# Cyber_VCM.net
KiCad netlist of a schematic drawn in Altium Designer
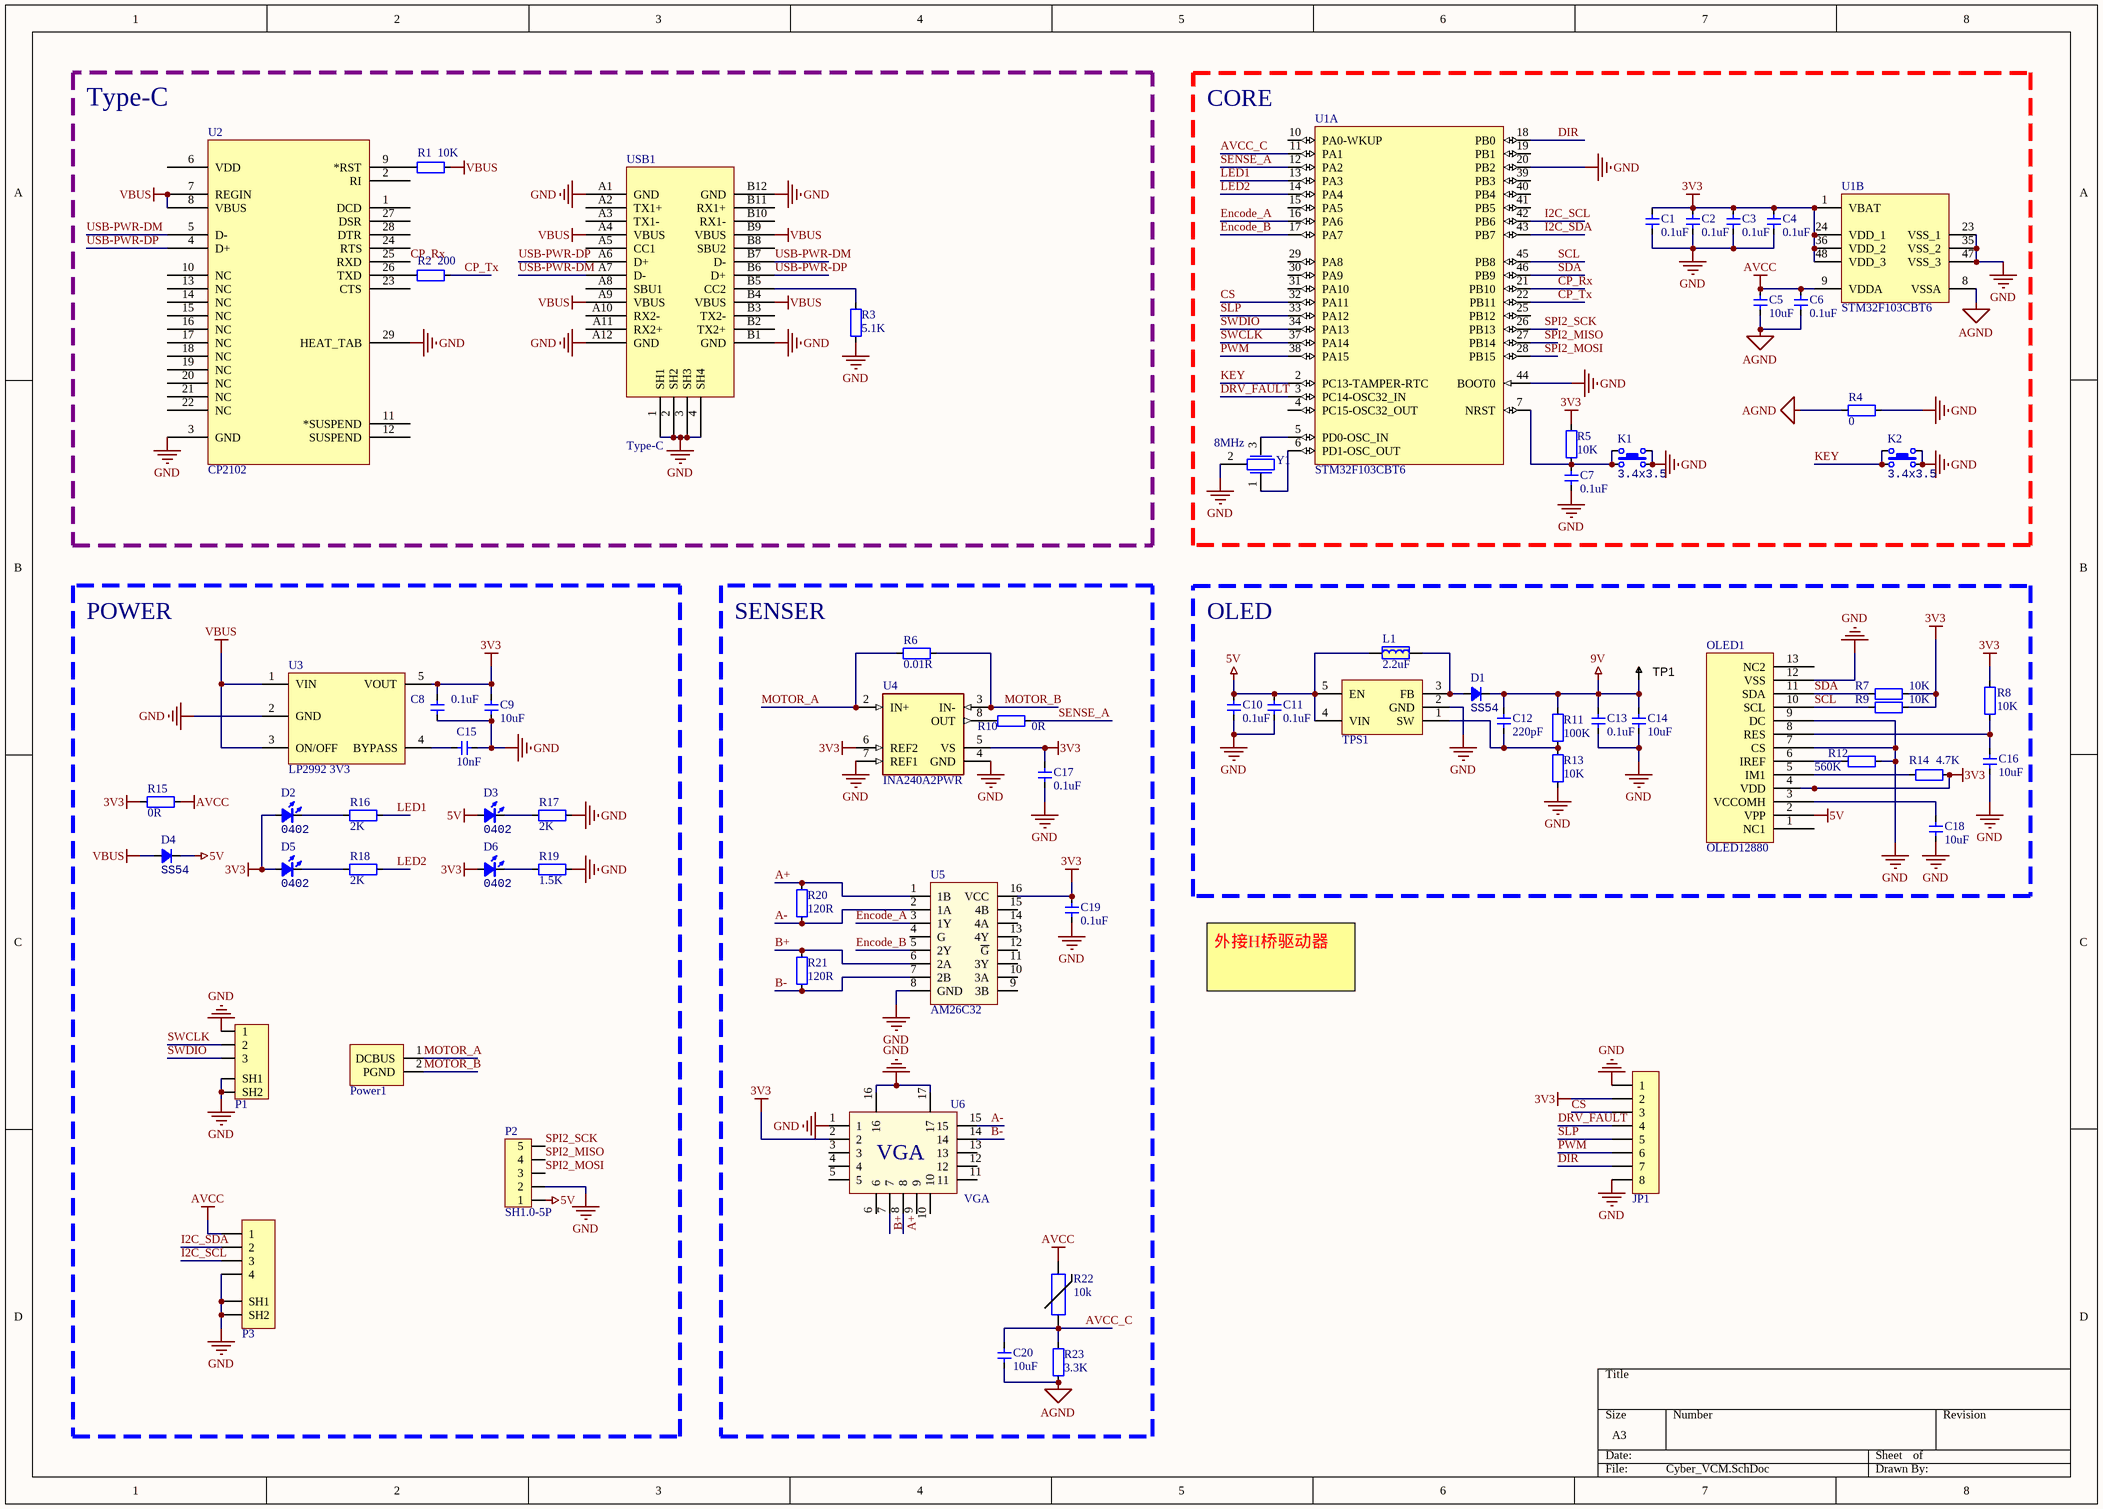
[diagram p0: Cyber_VCM.SchDoc]

(export (version "E")
  (design (tool "Eeschema 10.0.6"))
  (components
    (comp (ref "C1")
      (value "0.1uF")
      (footprint "CAP_0402")
      (description "Capacitor")
      (libsource (lib "Cyber_VCM") (part "电容-0402"))
    )
    (comp (ref "C2")
      (value "0.1uF")
      (footprint "CAP_0402")
      (description "Capacitor")
      (libsource (lib "Cyber_VCM") (part "电容-0402"))
    )
    (comp (ref "C3")
      (value "0.1uF")
      (footprint "CAP_0402")
      (description "Capacitor")
      (libsource (lib "Cyber_VCM") (part "电容-0402"))
    )
    (comp (ref "C4")
      (value "0.1uF")
      (footprint "CAP_0402")
      (description "Capacitor")
      (libsource (lib "Cyber_VCM") (part "电容-0402"))
    )
    (comp (ref "C5")
      (value "10uF")
      (footprint "CAP_0402")
      (description "Capacitor")
      (libsource (lib "Cyber_VCM") (part "电容-0402"))
    )
    (comp (ref "C6")
      (value "0.1uF")
      (footprint "CAP_0402")
      (description "Capacitor")
      (libsource (lib "Cyber_VCM") (part "电容-0402"))
    )
    (comp (ref "C7")
      (value "0.1uF")
      (footprint "CAP_0402")
      (description "Capacitor")
      (libsource (lib "MyPcbLib") (part "电容-0402"))
    )
    (comp (ref "C8")
      (value "0.1uF")
      (footprint "CAP_0402")
      (description "Capacitor")
      (libsource (lib "Cyber_VCM") (part "电容-0402"))
    )
    (comp (ref "C9")
      (value "10uF")
      (footprint "CAP_0402")
      (description "Capacitor")
      (libsource (lib "Cyber_VCM") (part "电容-0402"))
    )
    (comp (ref "C10")
      (value "0.1uF")
      (footprint "CAP_0402")
      (description "Capacitor")
      (libsource (lib "Serena-Ctrl") (part "电容-0402"))
    )
    (comp (ref "C11")
      (value "0.1uF")
      (footprint "CAP_0402")
      (description "Capacitor")
      (libsource (lib "Serena-Ctrl") (part "电容-0402"))
    )
    (comp (ref "C12")
      (value "220pF")
      (footprint "CAP_0402")
      (description "Capacitor")
      (libsource (lib "Serena-Ctrl") (part "电容-0402"))
    )
    (comp (ref "C13")
      (value "0.1uF")
      (footprint "0603-CAP")
      (description "Capacitor")
      (libsource (lib "Serena-Ctrl") (part "电容-0603"))
    )
    (comp (ref "C14")
      (value "10uF")
      (footprint "0603-CAP")
      (description "Capacitor")
      (libsource (lib "Serena-Ctrl") (part "电容-0603"))
    )
    (comp (ref "C15")
      (value "10nF")
      (footprint "CAP_0402")
      (description "Capacitor")
      (libsource (lib "Cyber_VCM") (part "电容-0402"))
    )
    (comp (ref "C16")
      (value "10uF")
      (footprint "CAP_0402")
      (description "Capacitor")
      (libsource (lib "MyPcbLib") (part "电容-0402"))
    )
    (comp (ref "C17")
      (value "0.1uF")
      (footprint "CAP_0402")
      (description "Capacitor")
      (libsource (lib "MyPcbLib") (part "电容-0402"))
    )
    (comp (ref "C18")
      (value "10uF")
      (footprint "CAP_0402")
      (description "Capacitor")
      (libsource (lib "MyPcbLib") (part "电容-0402"))
    )
    (comp (ref "C19")
      (value "0.1uF")
      (footprint "0603-CAP")
      (description "Capacitor")
      (libsource (lib "VCM_Ctrl") (part "电容-0603"))
    )
    (comp (ref "C20")
      (value "10uF")
      (footprint "CAP_0402")
      (description "Capacitor")
      (libsource (lib "MyPcbLib") (part "电容-0402"))
    )
    (comp (ref "D1")
      (value "SS54")
      (footprint "DO-214AC")
      (description "Diode")
      (libsource (lib "Serena-Ctrl") (part "Diode_SMA"))
    )
    (comp (ref "D2")
      (value "color?")
      (footprint "LED_0402_BLUE")
      (description "LED")
      (fields (field (name "TYPE") "0402"))
      (libsource (lib "Cyber_VCM") (part "LED_0402"))
    )
    (comp (ref "D3")
      (value "color?")
      (footprint "LED_0402_BLUE")
      (description "LED")
      (fields (field (name "TYPE") "0402"))
      (libsource (lib "Cyber_VCM") (part "LED_0402"))
    )
    (comp (ref "D4")
      (value "SS54")
      (footprint "DO-214AC")
      (description "Diode")
      (libsource (lib "Cyber_VCM") (part "Diode_SMA"))
    )
    (comp (ref "D5")
      (value "color?")
      (footprint "LED_0402_BLUE")
      (description "LED")
      (fields (field (name "TYPE") "0402"))
      (libsource (lib "Cyber_VCM") (part "LED_0402"))
    )
    (comp (ref "D6")
      (value "color?")
      (footprint "LED_0402_BLUE")
      (description "LED")
      (fields (field (name "TYPE") "0402"))
      (libsource (lib "Cyber_VCM") (part "LED_0402"))
    )
    (comp (ref "JP1")
      (value "HDR-1X8")
      (footprint "HDR2.54-M-LI-8P")
      (description "8P接插件")
      (fields (field (name "版权归属") "源创客"))
      (libsource (lib "Cyber_VCM") (part "Header 8"))
    )
    (comp (ref "K1")
      (value "3.4x3.5")
      (footprint "ButtonTACT_3.5*3.55_90")
      (description "Button")
      (fields (field (name "Comment") "TACT 4P"))
      (libsource (lib "KitSprout") (part "ButtonTACT"))
    )
    (comp (ref "K2")
      (value "3.4x3.5")
      (footprint "ButtonTACT_3.5*3.55_90")
      (description "Button")
      (fields (field (name "Comment") "TACT 4P"))
      (libsource (lib "KitSprout") (part "ButtonTACT"))
    )
    (comp (ref "L1")
      (value "2.2uF")
      (footprint "2520-L")
      (description "磁珠")
      (libsource (lib "Serena-Ctrl") (part "电感-0805"))
    )
    (comp (ref "OLED1")
      (value "OLED12880")
      (footprint "OLED12880")
      (description "12880寸OLED")
      (libsource (lib "Cyber_VCM") (part "OLED12880"))
    )
    (comp (ref "P1")
      (value "SH1.0-3P")
      (footprint "SH1.0-3P")
      (description "Header")
      (libsource (lib "Cyber_VCM") (part "SH1.0-3P"))
    )
    (comp (ref "P2") (value "SH1.0-5P") (footprint "SH1.0-5P") (libsource (lib "MyPcbLib") (part "SH1.0-5P")))
    (comp (ref "P3")
      (value "SH1.0-4P")
      (footprint "SH1.0-4P")
      (libsource (lib "Cyber_VCM") (part "SH1.0-4P"))
    )
    (comp (ref "Power1")
      (value "电源")
      (footprint "TX60电源")
      (description "12~24VDC电源")
      (libsource (lib "Cyber_VCM") (part "电源"))
    )
    (comp (ref "R1")
      (value "10K")
      (footprint "RES_0402")
      (description "Resistor")
      (libsource (lib "") (part "电阻-0402_1"))
    )
    (comp (ref "R2")
      (value "200")
      (footprint "RES_0402")
      (description "Resistor")
      (libsource (lib "") (part "电阻-0402_1"))
    )
    (comp (ref "R3")
      (value "5.1K")
      (footprint "RES_0402")
      (description "Resistor")
      (libsource (lib "") (part "电阻-0402_2"))
    )
    (comp (ref "R4")
      (value "0")
      (footprint "RES_0402")
      (description "Resistor")
      (libsource (lib "Cyber_VCM") (part "电阻-0402"))
    )
    (comp (ref "R5")
      (value "10K")
      (footprint "RES_0402")
      (description "Resistor")
      (libsource (lib "MyPcbLib") (part "电阻-0402"))
    )
    (comp (ref "R6")
      (value "0.01R")
      (footprint "1206-RES")
      (description "Resistor")
      (libsource (lib "MyPcbLib") (part "电阻-1206"))
    )
    (comp (ref "R7")
      (value "10K")
      (footprint "RES_0402")
      (description "Resistor")
      (libsource (lib "VectorController") (part "电阻-0402"))
    )
    (comp (ref "R8")
      (value "10K")
      (footprint "RES_0402")
      (description "Resistor")
      (libsource (lib "MyPcbLib") (part "电阻-0402"))
    )
    (comp (ref "R9")
      (value "10K")
      (footprint "RES_0402")
      (description "Resistor")
      (libsource (lib "VectorController") (part "电阻-0402"))
    )
    (comp (ref "R10")
      (value "0R")
      (footprint "RES_0402")
      (description "Resistor")
      (libsource (lib "Cyber_VCM") (part "电阻-0402"))
    )
    (comp (ref "R11")
      (value "100K")
      (footprint "RES_0402")
      (description "Resistor")
      (libsource (lib "Serena-Ctrl") (part "电阻-0402"))
    )
    (comp (ref "R12")
      (value "560K")
      (footprint "RES_0402")
      (description "Resistor")
      (libsource (lib "") (part "电阻-0402_3"))
    )
    (comp (ref "R13")
      (value "10K")
      (footprint "RES_0402")
      (description "Resistor")
      (libsource (lib "Serena-Ctrl") (part "电阻-0402"))
    )
    (comp (ref "R14")
      (value "4.7K")
      (footprint "RES_0402")
      (description "Resistor")
      (libsource (lib "") (part "电阻-0402_3"))
    )
    (comp (ref "R15")
      (value "0R")
      (footprint "RES_0402")
      (description "Resistor")
      (libsource (lib "") (part "电阻-0402_1"))
    )
    (comp (ref "R16")
      (value "2K")
      (footprint "RES_0402")
      (description "Resistor")
      (libsource (lib "Cyber_VCM") (part "电阻-0402"))
    )
    (comp (ref "R17")
      (value "2K")
      (footprint "RES_0402")
      (description "Resistor")
      (libsource (lib "Cyber_VCM") (part "电阻-0402"))
    )
    (comp (ref "R18")
      (value "2K")
      (footprint "RES_0402")
      (description "Resistor")
      (libsource (lib "Cyber_VCM") (part "电阻-0402"))
    )
    (comp (ref "R19")
      (value "1.5K")
      (footprint "RES_0402")
      (description "Resistor")
      (libsource (lib "Cyber_VCM") (part "电阻-0402"))
    )
    (comp (ref "R20")
      (value "120R")
      (footprint "RES_0603")
      (description "Resistor")
      (libsource (lib "Ctrl_FOC") (part "电阻-0603"))
    )
    (comp (ref "R21")
      (value "120R")
      (footprint "RES_0603")
      (description "Resistor")
      (libsource (lib "Ctrl_FOC") (part "电阻-0603"))
    )
    (comp (ref "R22")
      (value "10k")
      (footprint "RES_0402")
      (description "THERMISTOR 10K OHM NTC 0402 SMD")
      (fields (field (name "Comment") "NCP15XH103F03RC"))
      (libsource (lib "MyPcbLib") (part "NCP15XH103F03RC"))
    )
    (comp (ref "R23")
      (value "3.3K")
      (footprint "RES_0402")
      (description "Resistor")
      (libsource (lib "MyPcbLib") (part "电阻-0402"))
    )
    (comp (ref "TP1")
      (value "TESTPOINT")
      (footprint "TP-R30")
      (description "SMD test pin")
      (libsource (lib "Serena-Ctrl") (part "TESTPOINT"))
    )
    (comp (ref "TPS1")
      (value "TPS61040DBV")
      (footprint "SOT23-5")
      (libsource (lib "Serena-Ctrl") (part "TPS61040DBV"))
    )
    (comp (ref "U1")
      (value "STM32F103CBT6")
      (footprint "LQFP-48")
      (libsource (lib "Cyber_VCM") (part "STM32F103CBT6"))
    )
    (comp (ref "U2")
      (value "CP2102")
      (footprint "QFN-28")
      (description "USB转TTL")
      (libsource (lib "Cyber_VCM") (part "CP2102"))
    )
    (comp (ref "U3")
      (value "LP2992 3V3")
      (footprint "SOT23-5")
      (description "LDO")
      (libsource (lib "Cyber_VCM") (part "LP2992"))
    )
    (comp (ref "U4")
      (value "INA240A2PWR")
      (footprint "SOP65 P640X120-8N")
      (fields (field (name "MF") "Texas Instruments"))
      (libsource (lib "mLib") (part "INA240A2PWR"))
    )
    (comp (ref "U5")
      (value "AM26C32")
      (footprint "SOP16")
      (description "AM26C32 Quadruple Differential Line Receiver")
      (libsource (lib "VCM_Ctrl") (part "AM26C32"))
    )
    (comp (ref "U6") (value "VGA") (footprint "VGA15A") (libsource (lib "VCM_Ctrl") (part "VGA")))
    (comp (ref "USB1")
      (value "Type-C")
      (footprint "Type-C-TOP")
      (libsource (lib "Cyber_VCM") (part "USB-Type-C-TOP"))
    )
    (comp (ref "Y1")
      (value "8MHz")
      (footprint "晶振-3P")
      (description "村田贴片")
      (libsource (lib "MyPcbLib") (part "晶振-3Pin"))
    )
  )
  (nets
    (net (code "1") (name "/A+") (class "Default")
      (node (ref "R20") (pin "2") (pinfunction "2_2") (pintype "passive"))
      (node (ref "U5") (pin "1") (pinfunction "1B_1") (pintype "passive"))
      (node (ref "U6") (pin "8") (pinfunction "8_8") (pintype "passive"))
    )
    (net (code "2") (name "/A-") (class "Default")
      (node (ref "R20") (pin "1") (pinfunction "1_1") (pintype "passive"))
      (node (ref "U5") (pin "2") (pinfunction "1A_2") (pintype "passive"))
      (node (ref "U6") (pin "15") (pinfunction "15_15") (pintype "passive"))
    )
    (net (code "3") (name "/AVCC_C") (class "Default")
      (node (ref "C20") (pin "2") (pinfunction "2_2") (pintype "passive"))
      (node (ref "R22") (pin "1") (pinfunction "0_1") (pintype "passive"))
      (node (ref "R23") (pin "2") (pinfunction "2_2") (pintype "passive"))
      (node (ref "U1") (pin "11") (pinfunction "PA1_11") (pintype "bidirectional"))
    )
    (net (code "4") (name "/B+") (class "Default")
      (node (ref "R21") (pin "2") (pinfunction "2_2") (pintype "passive"))
      (node (ref "U5") (pin "6") (pinfunction "2A_6") (pintype "passive"))
      (node (ref "U6") (pin "7") (pinfunction "7_7") (pintype "passive"))
    )
    (net (code "5") (name "/B-") (class "Default")
      (node (ref "R21") (pin "1") (pinfunction "1_1") (pintype "passive"))
      (node (ref "U5") (pin "7") (pinfunction "2B_7") (pintype "passive"))
      (node (ref "U6") (pin "14") (pinfunction "14_14") (pintype "passive"))
    )
    (net (code "6") (name "/CP_Rx") (class "Default")
      (node (ref "U1") (pin "21") (pinfunction "PB10_21") (pintype "bidirectional"))
      (node (ref "U2") (pin "25") (pinfunction "RXD_25") (pintype "passive"))
    )
    (net (code "7") (name "/CP_Tx") (class "Default")
      (node (ref "R2") (pin "1") (pinfunction "1_1") (pintype "passive"))
      (node (ref "U1") (pin "22") (pinfunction "PB11_22") (pintype "bidirectional"))
    )
    (net (code "8") (name "/CS") (class "Default")
      (node (ref "JP1") (pin "3") (pinfunction "3_3") (pintype "passive"))
      (node (ref "U1") (pin "32") (pinfunction "PA11_32") (pintype "bidirectional"))
    )
    (net (code "9") (name "/DIR") (class "Default")
      (node (ref "JP1") (pin "7") (pinfunction "7_7") (pintype "passive"))
      (node (ref "U1") (pin "18") (pinfunction "PB0_18") (pintype "bidirectional"))
    )
    (net (code "10") (name "/DRV_FAULT") (class "Default")
      (node (ref "JP1") (pin "4") (pinfunction "4_4") (pintype "passive"))
      (node (ref "U1") (pin "3") (pinfunction "PC14-OSC32_IN_3") (pintype "bidirectional"))
    )
    (net (code "11") (name "/Encode_A") (class "Default")
      (node (ref "U1") (pin "16") (pinfunction "PA6_16") (pintype "bidirectional"))
      (node (ref "U5") (pin "3") (pinfunction "1Y_3") (pintype "passive"))
    )
    (net (code "12") (name "/Encode_B") (class "Default")
      (node (ref "U1") (pin "17") (pinfunction "PA7_17") (pintype "bidirectional"))
      (node (ref "U5") (pin "5") (pinfunction "2Y_5") (pintype "passive"))
    )
    (net (code "13") (name "/I2C_SCL") (class "Default")
      (node (ref "P3") (pin "3") (pinfunction "3_3") (pintype "passive"))
      (node (ref "U1") (pin "42") (pinfunction "PB6_42") (pintype "bidirectional"))
    )
    (net (code "14") (name "/I2C_SDA") (class "Default")
      (node (ref "P3") (pin "2") (pinfunction "2_2") (pintype "passive"))
      (node (ref "U1") (pin "43") (pinfunction "PB7_43") (pintype "bidirectional"))
    )
    (net (code "15") (name "/KEY") (class "Default")
      (node (ref "K2") (pin "1") (pinfunction "1_1") (pintype "passive"))
      (node (ref "K2") (pin "3") (pinfunction "3_3") (pintype "passive"))
      (node (ref "U1") (pin "2") (pinfunction "PC13-TAMPER-RTC_2") (pintype "bidirectional"))
    )
    (net (code "16") (name "/LED1") (class "Default")
      (node (ref "R16") (pin "2") (pinfunction "2_2") (pintype "passive"))
      (node (ref "U1") (pin "13") (pinfunction "PA3_13") (pintype "bidirectional"))
    )
    (net (code "17") (name "/LED2") (class "Default")
      (node (ref "R18") (pin "2") (pinfunction "2_2") (pintype "passive"))
      (node (ref "U1") (pin "14") (pinfunction "PA4_14") (pintype "bidirectional"))
    )
    (net (code "18") (name "/MOTOR_A") (class "Default")
      (node (ref "Power1") (pin "1") (pinfunction "DCBUS_1") (pintype "passive"))
      (node (ref "R6") (pin "1") (pinfunction "1_1") (pintype "passive"))
      (node (ref "U4") (pin "2") (pinfunction "IN+_2") (pintype "input"))
    )
    (net (code "19") (name "/MOTOR_B") (class "Default")
      (node (ref "Power1") (pin "2") (pinfunction "PGND_2") (pintype "passive"))
      (node (ref "R6") (pin "2") (pinfunction "2_2") (pintype "passive"))
      (node (ref "U4") (pin "3") (pinfunction "IN-_3") (pintype "input"))
    )
    (net (code "20") (name "/PWM") (class "Default")
      (node (ref "JP1") (pin "6") (pinfunction "6_6") (pintype "passive"))
      (node (ref "U1") (pin "38") (pinfunction "PA15_38") (pintype "bidirectional"))
    )
    (net (code "21") (name "/SCL") (class "Default")
      (node (ref "OLED1") (pin "10") (pinfunction "SCL_10") (pintype "passive"))
      (node (ref "R9") (pin "1") (pinfunction "1_1") (pintype "passive"))
      (node (ref "U1") (pin "45") (pinfunction "PB8_45") (pintype "bidirectional"))
    )
    (net (code "22") (name "/SDA") (class "Default")
      (node (ref "OLED1") (pin "11") (pinfunction "SDA_11") (pintype "passive"))
      (node (ref "R7") (pin "1") (pinfunction "1_1") (pintype "passive"))
      (node (ref "U1") (pin "46") (pinfunction "PB9_46") (pintype "bidirectional"))
    )
    (net (code "23") (name "/SENSE_A") (class "Default")
      (node (ref "R10") (pin "2") (pinfunction "2_2") (pintype "passive"))
      (node (ref "U1") (pin "12") (pinfunction "PA2_12") (pintype "bidirectional"))
    )
    (net (code "24") (name "/SLP") (class "Default")
      (node (ref "JP1") (pin "5") (pinfunction "5_5") (pintype "passive"))
      (node (ref "U1") (pin "33") (pinfunction "PA12_33") (pintype "bidirectional"))
    )
    (net (code "25") (name "/SPI2_MISO") (class "Default")
      (node (ref "P2") (pin "4") (pinfunction "4_4") (pintype "passive"))
      (node (ref "U1") (pin "27") (pinfunction "PB14_27") (pintype "bidirectional"))
    )
    (net (code "26") (name "/SPI2_MOSI") (class "Default")
      (node (ref "P2") (pin "3") (pinfunction "3_3") (pintype "passive"))
      (node (ref "U1") (pin "28") (pinfunction "PB15_28") (pintype "bidirectional"))
    )
    (net (code "27") (name "/SPI2_SCK") (class "Default")
      (node (ref "P2") (pin "5") (pinfunction "5_5") (pintype "passive"))
      (node (ref "U1") (pin "26") (pinfunction "PB13_26") (pintype "bidirectional"))
    )
    (net (code "28") (name "/SWCLK") (class "Default")
      (node (ref "P1") (pin "2") (pinfunction "2_2") (pintype "passive"))
      (node (ref "U1") (pin "37") (pinfunction "PA14_37") (pintype "bidirectional"))
    )
    (net (code "29") (name "/SWDIO") (class "Default")
      (node (ref "P1") (pin "3") (pinfunction "3_3") (pintype "passive"))
      (node (ref "U1") (pin "34") (pinfunction "PA13_34") (pintype "bidirectional"))
    )
    (net (code "30") (name "/USB-PWR-DM") (class "Default")
      (node (ref "U2") (pin "5") (pinfunction "D-_5") (pintype "passive"))
      (node (ref "USB1") (pin "A7") (pinfunction "D-_A7") (pintype "passive"))
      (node (ref "USB1") (pin "B7") (pinfunction "D-_B7") (pintype "passive"))
    )
    (net (code "31") (name "/USB-PWR-DP") (class "Default")
      (node (ref "U2") (pin "4") (pinfunction "D+_4") (pintype "passive"))
      (node (ref "USB1") (pin "A6") (pinfunction "D+_A6") (pintype "passive"))
      (node (ref "USB1") (pin "B6") (pinfunction "D+_B6") (pintype "passive"))
    )
    (net (code "32") (name "3V3") (class "Default")
      (node (ref "C1") (pin "2") (pinfunction "2_2") (pintype "passive"))
      (node (ref "C17") (pin "2") (pinfunction "2_2") (pintype "passive"))
      (node (ref "C19") (pin "2") (pinfunction "2_2") (pintype "passive"))
      (node (ref "C2") (pin "2") (pinfunction "2_2") (pintype "passive"))
      (node (ref "C3") (pin "2") (pinfunction "2_2") (pintype "passive"))
      (node (ref "C4") (pin "2") (pinfunction "2_2") (pintype "passive"))
      (node (ref "C8") (pin "2") (pinfunction "2_2") (pintype "passive"))
      (node (ref "C9") (pin "2") (pinfunction "2_2") (pintype "passive"))
      (node (ref "D2") (pin "1") (pinfunction "A_1") (pintype "passive"))
      (node (ref "D5") (pin "1") (pinfunction "A_1") (pintype "passive"))
      (node (ref "D6") (pin "1") (pinfunction "A_1") (pintype "passive"))
      (node (ref "JP1") (pin "2") (pinfunction "2_2") (pintype "passive"))
      (node (ref "OLED1") (pin "4") (pinfunction "VDD_4") (pintype "passive"))
      (node (ref "R14") (pin "2") (pinfunction "2_2") (pintype "passive"))
      (node (ref "R15") (pin "2") (pinfunction "2_2") (pintype "passive"))
      (node (ref "R5") (pin "2") (pinfunction "2_2") (pintype "passive"))
      (node (ref "R7") (pin "2") (pinfunction "2_2") (pintype "passive"))
      (node (ref "R8") (pin "2") (pinfunction "2_2") (pintype "passive"))
      (node (ref "R9") (pin "2") (pinfunction "2_2") (pintype "passive"))
      (node (ref "U1") (pin "1") (pinfunction "VBAT_1") (pintype "power_in"))
      (node (ref "U1") (pin "24") (pinfunction "VDD_1_24") (pintype "power_in"))
      (node (ref "U1") (pin "36") (pinfunction "VDD_2_36") (pintype "power_in"))
      (node (ref "U1") (pin "48") (pinfunction "VDD_3_48") (pintype "power_in"))
      (node (ref "U3") (pin "5") (pinfunction "VOUT_5") (pintype "passive"))
      (node (ref "U4") (pin "5") (pinfunction "VS_5") (pintype "power_in"))
      (node (ref "U4") (pin "6") (pinfunction "REF2_6") (pintype "input"))
      (node (ref "U5") (pin "16") (pinfunction "VCC_16") (pintype "passive"))
      (node (ref "U6") (pin "2") (pinfunction "2_2") (pintype "passive"))
    )
    (net (code "33") (name "5V") (class "Default")
      (node (ref "C10") (pin "2") (pinfunction "2_2") (pintype "passive"))
      (node (ref "C11") (pin "2") (pinfunction "2_2") (pintype "passive"))
      (node (ref "D3") (pin "1") (pinfunction "A_1") (pintype "passive"))
      (node (ref "D4") (pin "2") (pinfunction "K_2") (pintype "passive"))
      (node (ref "L1") (pin "1") (pintype "passive"))
      (node (ref "OLED1") (pin "2") (pinfunction "VPP_2") (pintype "passive"))
      (node (ref "P2") (pin "1") (pinfunction "1_1") (pintype "passive"))
      (node (ref "TPS1") (pin "4") (pinfunction "VIN_4") (pintype "passive"))
      (node (ref "TPS1") (pin "5") (pinfunction "EN_5") (pintype "passive"))
    )
    (net (code "34") (name "9V") (class "Default")
      (node (ref "C12") (pin "2") (pinfunction "2_2") (pintype "passive"))
      (node (ref "C13") (pin "2") (pinfunction "2_2") (pintype "passive"))
      (node (ref "C14") (pin "2") (pinfunction "2_2") (pintype "passive"))
      (node (ref "D1") (pin "2") (pinfunction "K_2") (pintype "passive"))
      (node (ref "R11") (pin "2") (pinfunction "2_2") (pintype "passive"))
      (node (ref "TP1") (pin "1") (pintype "passive"))
    )
    (net (code "35") (name "AGND") (class "Default")
      (node (ref "C20") (pin "1") (pinfunction "1_1") (pintype "passive"))
      (node (ref "C5") (pin "1") (pinfunction "1_1") (pintype "passive"))
      (node (ref "C6") (pin "1") (pinfunction "1_1") (pintype "passive"))
      (node (ref "R23") (pin "1") (pinfunction "1_1") (pintype "passive"))
      (node (ref "R4") (pin "1") (pinfunction "1_1") (pintype "passive"))
      (node (ref "U1") (pin "8") (pinfunction "VSSA_8") (pintype "power_in"))
    )
    (net (code "36") (name "AVCC") (class "Default")
      (node (ref "C5") (pin "2") (pinfunction "2_2") (pintype "passive"))
      (node (ref "C6") (pin "2") (pinfunction "2_2") (pintype "passive"))
      (node (ref "P3") (pin "1") (pinfunction "1_1") (pintype "passive"))
      (node (ref "R15") (pin "1") (pinfunction "1_1") (pintype "passive"))
      (node (ref "R22") (pin "2") (pinfunction "0_2") (pintype "passive"))
      (node (ref "U1") (pin "9") (pinfunction "VDDA_9") (pintype "power_in"))
    )
    (net (code "37") (name "GND") (class "Default")
      (node (ref "C1") (pin "1") (pinfunction "1_1") (pintype "passive"))
      (node (ref "C10") (pin "1") (pinfunction "1_1") (pintype "passive"))
      (node (ref "C11") (pin "1") (pinfunction "1_1") (pintype "passive"))
      (node (ref "C13") (pin "1") (pinfunction "1_1") (pintype "passive"))
      (node (ref "C14") (pin "1") (pinfunction "1_1") (pintype "passive"))
      (node (ref "C15") (pin "2") (pinfunction "2_2") (pintype "passive"))
      (node (ref "C16") (pin "1") (pinfunction "1_1") (pintype "passive"))
      (node (ref "C17") (pin "1") (pinfunction "1_1") (pintype "passive"))
      (node (ref "C18") (pin "1") (pinfunction "1_1") (pintype "passive"))
      (node (ref "C19") (pin "1") (pinfunction "1_1") (pintype "passive"))
      (node (ref "C2") (pin "1") (pinfunction "1_1") (pintype "passive"))
      (node (ref "C3") (pin "1") (pinfunction "1_1") (pintype "passive"))
      (node (ref "C4") (pin "1") (pinfunction "1_1") (pintype "passive"))
      (node (ref "C7") (pin "1") (pinfunction "1_1") (pintype "passive"))
      (node (ref "C8") (pin "1") (pinfunction "1_1") (pintype "passive"))
      (node (ref "C9") (pin "1") (pinfunction "1_1") (pintype "passive"))
      (node (ref "JP1") (pin "1") (pinfunction "1_1") (pintype "passive"))
      (node (ref "JP1") (pin "8") (pinfunction "8_8") (pintype "passive"))
      (node (ref "K1") (pin "2") (pinfunction "2_2") (pintype "passive"))
      (node (ref "K1") (pin "4") (pinfunction "4_4") (pintype "passive"))
      (node (ref "K2") (pin "2") (pinfunction "2_2") (pintype "passive"))
      (node (ref "K2") (pin "4") (pinfunction "4_4") (pintype "passive"))
      (node (ref "OLED1") (pin "12") (pinfunction "VSS_12") (pintype "passive"))
      (node (ref "OLED1") (pin "7") (pinfunction "CS_7") (pintype "passive"))
      (node (ref "OLED1") (pin "9") (pinfunction "DC_9") (pintype "passive"))
      (node (ref "P1") (pin "1") (pinfunction "1_1") (pintype "passive"))
      (node (ref "P1") (pin "SH1") (pinfunction "SH1_SH1") (pintype "passive"))
      (node (ref "P1") (pin "SH2") (pinfunction "SH2_SH2") (pintype "passive"))
      (node (ref "P2") (pin "2") (pinfunction "2_2") (pintype "passive"))
      (node (ref "P3") (pin "4") (pinfunction "4_4") (pintype "passive"))
      (node (ref "P3") (pin "SH1") (pinfunction "SH1_SH1") (pintype "passive"))
      (node (ref "P3") (pin "SH2") (pinfunction "SH2_SH2") (pintype "passive"))
      (node (ref "R12") (pin "2") (pinfunction "2_2") (pintype "passive"))
      (node (ref "R13") (pin "1") (pinfunction "1_1") (pintype "passive"))
      (node (ref "R17") (pin "2") (pinfunction "2_2") (pintype "passive"))
      (node (ref "R19") (pin "2") (pinfunction "2_2") (pintype "passive"))
      (node (ref "R3") (pin "2") (pinfunction "2_2") (pintype "passive"))
      (node (ref "R4") (pin "2") (pinfunction "2_2") (pintype "passive"))
      (node (ref "TPS1") (pin "2") (pinfunction "GND_2") (pintype "passive"))
      (node (ref "U1") (pin "20") (pinfunction "PB2_20") (pintype "bidirectional"))
      (node (ref "U1") (pin "23") (pinfunction "VSS_1_23") (pintype "power_in"))
      (node (ref "U1") (pin "35") (pinfunction "VSS_2_35") (pintype "power_in"))
      (node (ref "U1") (pin "44") (pinfunction "BOOT0_44") (pintype "input"))
      (node (ref "U1") (pin "47") (pinfunction "VSS_3_47") (pintype "power_in"))
      (node (ref "U2") (pin "29") (pinfunction "HEAT_TAB_29") (pintype "passive"))
      (node (ref "U2") (pin "3") (pinfunction "GND_3") (pintype "passive"))
      (node (ref "U3") (pin "2") (pinfunction "GND_2") (pintype "passive"))
      (node (ref "U4") (pin "4") (pinfunction "GND_4") (pintype "power_in"))
      (node (ref "U4") (pin "7") (pinfunction "REF1_7") (pintype "input"))
      (node (ref "U5") (pin "8") (pinfunction "GND_8") (pintype "passive"))
      (node (ref "U6") (pin "1") (pinfunction "1_1") (pintype "passive"))
      (node (ref "U6") (pin "16") (pinfunction "16_16") (pintype "passive"))
      (node (ref "U6") (pin "17") (pinfunction "17_17") (pintype "passive"))
      (node (ref "USB1") (pin "1") (pinfunction "SH1_1") (pintype "passive"))
      (node (ref "USB1") (pin "2") (pinfunction "SH2_2") (pintype "passive"))
      (node (ref "USB1") (pin "3") (pinfunction "SH3_3") (pintype "passive"))
      (node (ref "USB1") (pin "4") (pinfunction "SH4_4") (pintype "passive"))
      (node (ref "USB1") (pin "A1") (pinfunction "GND_A1") (pintype "passive"))
      (node (ref "USB1") (pin "A12") (pinfunction "GND_A12") (pintype "passive"))
      (node (ref "USB1") (pin "B1") (pinfunction "GND_B1") (pintype "passive"))
      (node (ref "USB1") (pin "B12") (pinfunction "GND_B12") (pintype "passive"))
      (node (ref "Y1") (pin "2") (pinfunction "2_2") (pintype "passive"))
    )
    (net (code "38") (name "Net-(D1-A)") (class "Default")
      (node (ref "D1") (pin "1") (pinfunction "A_1") (pintype "passive"))
      (node (ref "L1") (pin "2") (pinfunction "2_2") (pintype "passive"))
      (node (ref "TPS1") (pin "3") (pinfunction "FB_3") (pintype "passive"))
    )
    (net (code "39") (name "Net-(D2-K)") (class "Default")
      (node (ref "D2") (pin "2") (pinfunction "K_2") (pintype "passive"))
      (node (ref "R16") (pin "1") (pinfunction "1_1") (pintype "passive"))
    )
    (net (code "40") (name "Net-(D3-K)") (class "Default")
      (node (ref "D3") (pin "2") (pinfunction "K_2") (pintype "passive"))
      (node (ref "R17") (pin "1") (pinfunction "1_1") (pintype "passive"))
    )
    (net (code "41") (name "Net-(D5-K)") (class "Default")
      (node (ref "D5") (pin "2") (pinfunction "K_2") (pintype "passive"))
      (node (ref "R18") (pin "1") (pinfunction "1_1") (pintype "passive"))
    )
    (net (code "42") (name "Net-(D6-K)") (class "Default")
      (node (ref "D6") (pin "2") (pinfunction "K_2") (pintype "passive"))
      (node (ref "R19") (pin "1") (pinfunction "1_1") (pintype "passive"))
    )
    (net (code "43") (name "Net-(OLED1-IM1)") (class "Default")
      (node (ref "OLED1") (pin "5") (pinfunction "IM1_5") (pintype "passive"))
      (node (ref "R14") (pin "1") (pinfunction "1_1") (pintype "passive"))
    )
    (net (code "44") (name "Net-(OLED1-IREF)") (class "Default")
      (node (ref "OLED1") (pin "6") (pinfunction "IREF_6") (pintype "passive"))
      (node (ref "R12") (pin "1") (pinfunction "1_1") (pintype "passive"))
    )
    (net (code "45") (name "Net-(OLED1-RES)") (class "Default")
      (node (ref "C16") (pin "2") (pinfunction "2_2") (pintype "passive"))
      (node (ref "OLED1") (pin "8") (pinfunction "RES_8") (pintype "passive"))
      (node (ref "R8") (pin "1") (pinfunction "1_1") (pintype "passive"))
    )
    (net (code "46") (name "Net-(OLED1-VCCOMH)") (class "Default")
      (node (ref "C18") (pin "2") (pinfunction "2_2") (pintype "passive"))
      (node (ref "OLED1") (pin "3") (pinfunction "VCCOMH_3") (pintype "passive"))
    )
    (net (code "47") (name "Net-(TPS1-SW)") (class "Default")
      (node (ref "C12") (pin "1") (pinfunction "1_1") (pintype "passive"))
      (node (ref "R11") (pin "1") (pinfunction "1_1") (pintype "passive"))
      (node (ref "R13") (pin "2") (pinfunction "2_2") (pintype "passive"))
      (node (ref "TPS1") (pin "1") (pinfunction "SW_1") (pintype "passive"))
    )
    (net (code "48") (name "Net-(U1A-NRST)") (class "Default")
      (node (ref "C7") (pin "2") (pinfunction "2_2") (pintype "passive"))
      (node (ref "K1") (pin "1") (pinfunction "1_1") (pintype "passive"))
      (node (ref "K1") (pin "3") (pinfunction "3_3") (pintype "passive"))
      (node (ref "R5") (pin "1") (pinfunction "1_1") (pintype "passive"))
      (node (ref "U1") (pin "7") (pinfunction "NRST_7") (pintype "bidirectional"))
    )
    (net (code "49") (name "Net-(U1A-PD0-OSC_IN)") (class "Default")
      (node (ref "U1") (pin "5") (pinfunction "PD0-OSC_IN_5") (pintype "bidirectional"))
      (node (ref "Y1") (pin "3") (pinfunction "3_3") (pintype "passive"))
    )
    (net (code "50") (name "Net-(U1A-PD1-OSC_OUT)") (class "Default")
      (node (ref "U1") (pin "6") (pinfunction "PD1-OSC_OUT_6") (pintype "bidirectional"))
      (node (ref "Y1") (pin "1") (pinfunction "1_1") (pintype "passive"))
    )
    (net (code "51") (name "Net-(U2-*RST)") (class "Default")
      (node (ref "R1") (pin "2") (pinfunction "2_2") (pintype "passive"))
      (node (ref "U2") (pin "9") (pinfunction "*RST_9") (pintype "passive"))
    )
    (net (code "52") (name "Net-(U2-TXD)") (class "Default")
      (node (ref "R2") (pin "2") (pinfunction "2_2") (pintype "passive"))
      (node (ref "U2") (pin "26") (pinfunction "TXD_26") (pintype "passive"))
    )
    (net (code "53") (name "Net-(U3-BYPASS)") (class "Default")
      (node (ref "C15") (pin "1") (pinfunction "1_1") (pintype "passive"))
      (node (ref "U3") (pin "4") (pinfunction "BYPASS_4") (pintype "passive"))
    )
    (net (code "54") (name "Net-(U4-OUT)") (class "Default")
      (node (ref "R10") (pin "1") (pinfunction "1_1") (pintype "passive"))
      (node (ref "U4") (pin "8") (pinfunction "OUT_8") (pintype "output"))
    )
    (net (code "55") (name "Net-(USB1-CC2)") (class "Default")
      (node (ref "R3") (pin "1") (pinfunction "1_1") (pintype "passive"))
      (node (ref "USB1") (pin "B5") (pinfunction "CC2_B5") (pintype "passive"))
    )
    (net (code "56") (name "VBUS") (class "Default")
      (node (ref "D4") (pin "1") (pinfunction "A_1") (pintype "passive"))
      (node (ref "R1") (pin "1") (pinfunction "1_1") (pintype "passive"))
      (node (ref "U2") (pin "7") (pinfunction "REGIN_7") (pintype "passive"))
      (node (ref "U2") (pin "8") (pinfunction "VBUS_8") (pintype "passive"))
      (node (ref "U3") (pin "1") (pinfunction "VIN_1") (pintype "passive"))
      (node (ref "U3") (pin "3") (pinfunction "ON/OFF_3") (pintype "passive"))
      (node (ref "USB1") (pin "A4") (pinfunction "VBUS_A4") (pintype "passive"))
      (node (ref "USB1") (pin "A9") (pinfunction "VBUS_A9") (pintype "passive"))
      (node (ref "USB1") (pin "B4") (pinfunction "VBUS_B4") (pintype "passive"))
      (node (ref "USB1") (pin "B9") (pinfunction "VBUS_B9") (pintype "passive"))
    )
    (net (code "57") (name "unconnected-(OLED1-NC1-Pad1)") (class "Default")
      (node (ref "OLED1") (pin "1") (pinfunction "NC1_1") (pintype "passive"))
    )
    (net (code "58") (name "unconnected-(OLED1-NC2-Pad13)") (class "Default")
      (node (ref "OLED1") (pin "13") (pinfunction "NC2_13") (pintype "passive"))
    )
    (net (code "59") (name "unconnected-(U1A-PA0-WKUP-Pad10)") (class "Default")
      (node (ref "U1") (pin "10") (pinfunction "PA0-WKUP_10") (pintype "bidirectional"))
    )
    (net (code "60") (name "unconnected-(U1A-PA5-Pad15)") (class "Default")
      (node (ref "U1") (pin "15") (pinfunction "PA5_15") (pintype "bidirectional"))
    )
    (net (code "61") (name "unconnected-(U1A-PA8-Pad29)") (class "Default")
      (node (ref "U1") (pin "29") (pinfunction "PA8_29") (pintype "bidirectional"))
    )
    (net (code "62") (name "unconnected-(U1A-PA9-Pad30)") (class "Default")
      (node (ref "U1") (pin "30") (pinfunction "PA9_30") (pintype "bidirectional"))
    )
    (net (code "63") (name "unconnected-(U1A-PA10-Pad31)") (class "Default")
      (node (ref "U1") (pin "31") (pinfunction "PA10_31") (pintype "bidirectional"))
    )
    (net (code "64") (name "unconnected-(U1A-PB1-Pad19)") (class "Default")
      (node (ref "U1") (pin "19") (pinfunction "PB1_19") (pintype "bidirectional"))
    )
    (net (code "65") (name "unconnected-(U1A-PB3-Pad39)") (class "Default")
      (node (ref "U1") (pin "39") (pinfunction "PB3_39") (pintype "bidirectional"))
    )
    (net (code "66") (name "unconnected-(U1A-PB4-Pad40)") (class "Default")
      (node (ref "U1") (pin "40") (pinfunction "PB4_40") (pintype "bidirectional"))
    )
    (net (code "67") (name "unconnected-(U1A-PB5-Pad41)") (class "Default")
      (node (ref "U1") (pin "41") (pinfunction "PB5_41") (pintype "bidirectional"))
    )
    (net (code "68") (name "unconnected-(U1A-PB12-Pad25)") (class "Default")
      (node (ref "U1") (pin "25") (pinfunction "PB12_25") (pintype "bidirectional"))
    )
    (net (code "69") (name "unconnected-(U1A-PC15-OSC32_OUT-Pad4)") (class "Default")
      (node (ref "U1") (pin "4") (pinfunction "PC15-OSC32_OUT_4") (pintype "bidirectional"))
    )
    (net (code "70") (name "unconnected-(U2-*SUSPEND-Pad11)") (class "Default")
      (node (ref "U2") (pin "11") (pinfunction "*SUSPEND_11") (pintype "passive"))
    )
    (net (code "71") (name "unconnected-(U2-CTS-Pad23)") (class "Default")
      (node (ref "U2") (pin "23") (pinfunction "CTS_23") (pintype "passive"))
    )
    (net (code "72") (name "unconnected-(U2-DCD-Pad1)") (class "Default")
      (node (ref "U2") (pin "1") (pinfunction "DCD_1") (pintype "passive"))
    )
    (net (code "73") (name "unconnected-(U2-DSR-Pad27)") (class "Default")
      (node (ref "U2") (pin "27") (pinfunction "DSR_27") (pintype "passive"))
    )
    (net (code "74") (name "unconnected-(U2-DTR-Pad28)") (class "Default")
      (node (ref "U2") (pin "28") (pinfunction "DTR_28") (pintype "passive"))
    )
    (net (code "75") (name "unconnected-(U2-NC-Pad10)") (class "Default")
      (node (ref "U2") (pin "10") (pinfunction "NC_10") (pintype "passive"))
    )
    (net (code "76") (name "unconnected-(U2-NC-Pad13)") (class "Default")
      (node (ref "U2") (pin "13") (pinfunction "NC_13") (pintype "passive"))
    )
    (net (code "77") (name "unconnected-(U2-NC-Pad14)") (class "Default")
      (node (ref "U2") (pin "14") (pinfunction "NC_14") (pintype "passive"))
    )
    (net (code "78") (name "unconnected-(U2-NC-Pad15)") (class "Default")
      (node (ref "U2") (pin "15") (pinfunction "NC_15") (pintype "passive"))
    )
    (net (code "79") (name "unconnected-(U2-NC-Pad16)") (class "Default")
      (node (ref "U2") (pin "16") (pinfunction "NC_16") (pintype "passive"))
    )
    (net (code "80") (name "unconnected-(U2-NC-Pad17)") (class "Default")
      (node (ref "U2") (pin "17") (pinfunction "NC_17") (pintype "passive"))
    )
    (net (code "81") (name "unconnected-(U2-NC-Pad18)") (class "Default")
      (node (ref "U2") (pin "18") (pinfunction "NC_18") (pintype "passive"))
    )
    (net (code "82") (name "unconnected-(U2-NC-Pad19)") (class "Default")
      (node (ref "U2") (pin "19") (pinfunction "NC_19") (pintype "passive"))
    )
    (net (code "83") (name "unconnected-(U2-NC-Pad20)") (class "Default")
      (node (ref "U2") (pin "20") (pinfunction "NC_20") (pintype "passive"))
    )
    (net (code "84") (name "unconnected-(U2-NC-Pad21)") (class "Default")
      (node (ref "U2") (pin "21") (pinfunction "NC_21") (pintype "passive"))
    )
    (net (code "85") (name "unconnected-(U2-NC-Pad22)") (class "Default")
      (node (ref "U2") (pin "22") (pinfunction "NC_22") (pintype "passive"))
    )
    (net (code "86") (name "unconnected-(U2-RI-Pad2)") (class "Default")
      (node (ref "U2") (pin "2") (pinfunction "RI_2") (pintype "passive"))
    )
    (net (code "87") (name "unconnected-(U2-RTS-Pad24)") (class "Default")
      (node (ref "U2") (pin "24") (pinfunction "RTS_24") (pintype "passive"))
    )
    (net (code "88") (name "unconnected-(U2-SUSPEND-Pad12)") (class "Default")
      (node (ref "U2") (pin "12") (pinfunction "SUSPEND_12") (pintype "passive"))
    )
    (net (code "89") (name "unconnected-(U2-VDD-Pad6)") (class "Default")
      (node (ref "U2") (pin "6") (pinfunction "VDD_6") (pintype "passive"))
    )
    (net (code "90") (name "unconnected-(U5-3A-Pad10)") (class "Default")
      (node (ref "U5") (pin "10") (pinfunction "3A_10") (pintype "passive"))
    )
    (net (code "91") (name "unconnected-(U5-3B-Pad9)") (class "Default")
      (node (ref "U5") (pin "9") (pinfunction "3B_9") (pintype "passive"))
    )
    (net (code "92") (name "unconnected-(U5-3Y-Pad11)") (class "Default")
      (node (ref "U5") (pin "11") (pinfunction "3Y_11") (pintype "passive"))
    )
    (net (code "93") (name "unconnected-(U5-4A-Pad14)") (class "Default")
      (node (ref "U5") (pin "14") (pinfunction "4A_14") (pintype "passive"))
    )
    (net (code "94") (name "unconnected-(U5-4B-Pad15)") (class "Default")
      (node (ref "U5") (pin "15") (pinfunction "4B_15") (pintype "passive"))
    )
    (net (code "95") (name "unconnected-(U5-4Y-Pad13)") (class "Default")
      (node (ref "U5") (pin "13") (pinfunction "4Y_13") (pintype "passive"))
    )
    (net (code "96") (name "unconnected-(U5-G-Pad4)") (class "Default")
      (node (ref "U5") (pin "4") (pinfunction "G_4") (pintype "passive"))
    )
    (net (code "97") (name "unconnected-(U5-~{G}-Pad12)") (class "Default")
      (node (ref "U5") (pin "12") (pinfunction "~{G}_12") (pintype "passive"))
    )
    (net (code "98") (name "unconnected-(U6-Pad3)") (class "Default")
      (node (ref "U6") (pin "3") (pinfunction "3_3") (pintype "passive"))
    )
    (net (code "99") (name "unconnected-(U6-Pad4)") (class "Default")
      (node (ref "U6") (pin "4") (pinfunction "4_4") (pintype "passive"))
    )
    (net (code "100") (name "unconnected-(U6-Pad5)") (class "Default")
      (node (ref "U6") (pin "5") (pinfunction "5_5") (pintype "passive"))
    )
    (net (code "101") (name "unconnected-(U6-Pad6)") (class "Default")
      (node (ref "U6") (pin "6") (pinfunction "6_6") (pintype "passive"))
    )
    (net (code "102") (name "unconnected-(U6-Pad9)") (class "Default")
      (node (ref "U6") (pin "9") (pinfunction "9_9") (pintype "passive"))
    )
    (net (code "103") (name "unconnected-(U6-Pad10)") (class "Default")
      (node (ref "U6") (pin "10") (pinfunction "10_10") (pintype "passive"))
    )
    (net (code "104") (name "unconnected-(U6-Pad11)") (class "Default")
      (node (ref "U6") (pin "11") (pinfunction "11_11") (pintype "passive"))
    )
    (net (code "105") (name "unconnected-(U6-Pad12)") (class "Default")
      (node (ref "U6") (pin "12") (pinfunction "12_12") (pintype "passive"))
    )
    (net (code "106") (name "unconnected-(U6-Pad13)") (class "Default")
      (node (ref "U6") (pin "13") (pinfunction "13_13") (pintype "passive"))
    )
    (net (code "107") (name "unconnected-(USB1-CC1-PadA5)") (class "Default")
      (node (ref "USB1") (pin "A5") (pinfunction "CC1_A5") (pintype "passive"))
    )
    (net (code "108") (name "unconnected-(USB1-RX1+-PadB11)") (class "Default")
      (node (ref "USB1") (pin "B11") (pinfunction "RX1+_B11") (pintype "passive"))
    )
    (net (code "109") (name "unconnected-(USB1-RX1--PadB10)") (class "Default")
      (node (ref "USB1") (pin "B10") (pinfunction "RX1-_B10") (pintype "passive"))
    )
    (net (code "110") (name "unconnected-(USB1-RX2+-PadA11)") (class "Default")
      (node (ref "USB1") (pin "A11") (pinfunction "RX2+_A11") (pintype "passive"))
    )
    (net (code "111") (name "unconnected-(USB1-RX2--PadA10)") (class "Default")
      (node (ref "USB1") (pin "A10") (pinfunction "RX2-_A10") (pintype "passive"))
    )
    (net (code "112") (name "unconnected-(USB1-SBU1-PadA8)") (class "Default")
      (node (ref "USB1") (pin "A8") (pinfunction "SBU1_A8") (pintype "passive"))
    )
    (net (code "113") (name "unconnected-(USB1-SBU2-PadB8)") (class "Default")
      (node (ref "USB1") (pin "B8") (pinfunction "SBU2_B8") (pintype "passive"))
    )
    (net (code "114") (name "unconnected-(USB1-TX1+-PadA2)") (class "Default")
      (node (ref "USB1") (pin "A2") (pinfunction "TX1+_A2") (pintype "passive"))
    )
    (net (code "115") (name "unconnected-(USB1-TX1--PadA3)") (class "Default")
      (node (ref "USB1") (pin "A3") (pinfunction "TX1-_A3") (pintype "passive"))
    )
    (net (code "116") (name "unconnected-(USB1-TX2+-PadB2)") (class "Default")
      (node (ref "USB1") (pin "B2") (pinfunction "TX2+_B2") (pintype "passive"))
    )
    (net (code "117") (name "unconnected-(USB1-TX2--PadB3)") (class "Default")
      (node (ref "USB1") (pin "B3") (pinfunction "TX2-_B3") (pintype "passive"))
    )
  )
)
